# POWER_CON.net
KiCad netlist of a schematic drawn in Altium Designer
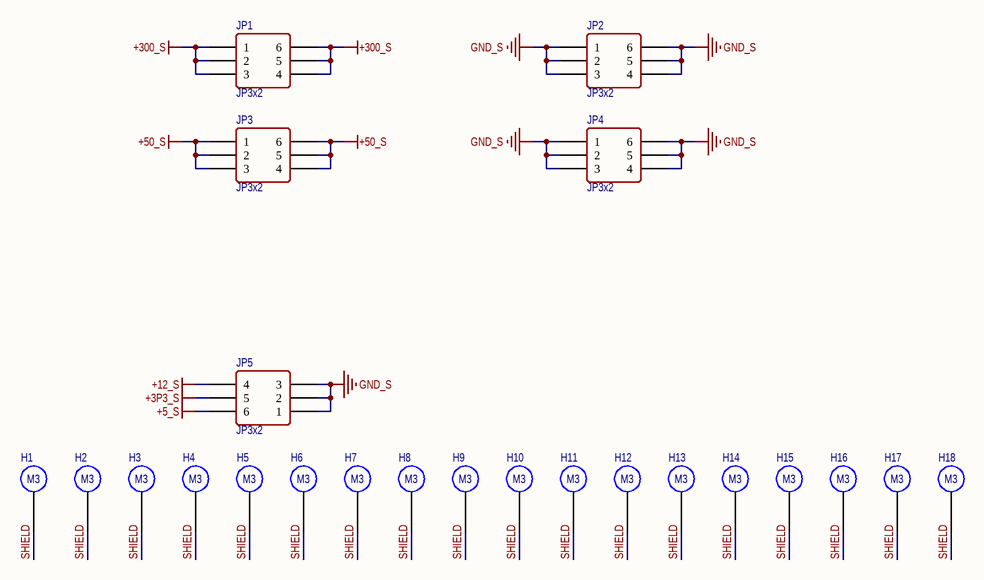
[diagram p0: POWER_CON.SchDoc]

(export (version "E")
  (design (tool "Eeschema 10.0.6"))
  (components
    (comp (ref "H1") (value "M3") (footprint "M3") (libsource (lib "Library") (part "M3")))
    (comp (ref "H2") (value "M3") (footprint "M3") (libsource (lib "Library") (part "M3")))
    (comp (ref "H3") (value "M3") (footprint "M3") (libsource (lib "Library") (part "M3")))
    (comp (ref "H4") (value "M3") (footprint "M3") (libsource (lib "Library") (part "M3")))
    (comp (ref "H5") (value "M3") (footprint "M3") (libsource (lib "Library") (part "M3")))
    (comp (ref "H6") (value "M3") (footprint "M3") (libsource (lib "Library") (part "M3")))
    (comp (ref "H7") (value "M3") (footprint "M3") (libsource (lib "Library") (part "M3")))
    (comp (ref "H8") (value "M3") (footprint "M3") (libsource (lib "Library") (part "M3")))
    (comp (ref "H9") (value "M3") (footprint "M3") (libsource (lib "Library") (part "M3")))
    (comp (ref "H10") (value "M3") (footprint "M3") (libsource (lib "Library") (part "M3")))
    (comp (ref "H11") (value "M3") (footprint "M3") (libsource (lib "Library") (part "M3")))
    (comp (ref "H12") (value "M3") (footprint "M3") (libsource (lib "Library") (part "M3")))
    (comp (ref "H13") (value "M3") (footprint "M3") (libsource (lib "Library") (part "M3")))
    (comp (ref "H14") (value "M3") (footprint "M3") (libsource (lib "Library") (part "M3")))
    (comp (ref "H15") (value "M3") (footprint "M3") (libsource (lib "Library") (part "M3")))
    (comp (ref "H16") (value "M3") (footprint "M3") (libsource (lib "Library") (part "M3")))
    (comp (ref "H17") (value "M3") (footprint "M3") (libsource (lib "Library") (part "M3")))
    (comp (ref "H18") (value "M3") (footprint "M3") (libsource (lib "Library") (part "M3")))
    (comp (ref "JP1")
      (value "JP3x2")
      (footprint "JP3-C2T")
      (description "CONN RCPT 6POS 0.1 GOLD PCB")
      (fields
        (field (name "MANUFACTURER") "Würth Elektronik eiSos GmbH")
        (field (name "PARTNO") "61300621821")
        (field (name "CREATED BY") "Karrer Zheng")
      )
      (libsource (lib "Library") (part "JP3x2"))
    )
    (comp (ref "JP2")
      (value "JP3x2")
      (footprint "JP3-C2T")
      (description "CONN RCPT 6POS 0.1 GOLD PCB")
      (fields
        (field (name "MANUFACTURER") "Würth Elektronik eiSos GmbH")
        (field (name "PARTNO") "61300621821")
        (field (name "CREATED BY") "Karrer Zheng")
      )
      (libsource (lib "Library") (part "JP3x2"))
    )
    (comp (ref "JP3")
      (value "JP3x2")
      (footprint "JP3-C2T")
      (description "CONN RCPT 6POS 0.1 GOLD PCB")
      (fields
        (field (name "MANUFACTURER") "Würth Elektronik eiSos GmbH")
        (field (name "PARTNO") "61300621821")
        (field (name "CREATED BY") "Karrer Zheng")
      )
      (libsource (lib "Library") (part "JP3x2"))
    )
    (comp (ref "JP4")
      (value "JP3x2")
      (footprint "JP3-C2T")
      (description "CONN RCPT 6POS 0.1 GOLD PCB")
      (fields
        (field (name "MANUFACTURER") "Würth Elektronik eiSos GmbH")
        (field (name "PARTNO") "61300621821")
        (field (name "CREATED BY") "Karrer Zheng")
      )
      (libsource (lib "Library") (part "JP3x2"))
    )
    (comp (ref "JP5")
      (value "JP3x2")
      (footprint "JP3-C2T")
      (description "CONN RCPT 6POS 0.1 GOLD PCB")
      (fields
        (field (name "MANUFACTURER") "Würth Elektronik eiSos GmbH")
        (field (name "PARTNO") "61300621821")
        (field (name "CREATED BY") "Karrer Zheng")
      )
      (libsource (lib "Library") (part "JP3x2"))
    )
  )
  (nets
    (net (code "1") (name "+3P3_S") (class "Default")
      (node (ref "JP5") (pin "5") (pinfunction "5_5") (pintype "passive"))
    )
    (net (code "2") (name "+5_S") (class "Default")
      (node (ref "JP5") (pin "6") (pinfunction "6_6") (pintype "passive"))
    )
    (net (code "3") (name "+12_S") (class "Default")
      (node (ref "JP5") (pin "4") (pinfunction "4_4") (pintype "passive"))
    )
    (net (code "4") (name "+50_S") (class "Default")
      (node (ref "JP3") (pin "1") (pinfunction "1_1") (pintype "passive"))
      (node (ref "JP3") (pin "2") (pinfunction "2_2") (pintype "passive"))
      (node (ref "JP3") (pin "3") (pinfunction "3_3") (pintype "passive"))
      (node (ref "JP3") (pin "4") (pinfunction "4_4") (pintype "passive"))
      (node (ref "JP3") (pin "5") (pinfunction "5_5") (pintype "passive"))
      (node (ref "JP3") (pin "6") (pinfunction "6_6") (pintype "passive"))
    )
    (net (code "5") (name "+300_S") (class "Default")
      (node (ref "JP1") (pin "1") (pinfunction "1_1") (pintype "passive"))
      (node (ref "JP1") (pin "2") (pinfunction "2_2") (pintype "passive"))
      (node (ref "JP1") (pin "3") (pinfunction "3_3") (pintype "passive"))
      (node (ref "JP1") (pin "4") (pinfunction "4_4") (pintype "passive"))
      (node (ref "JP1") (pin "5") (pinfunction "5_5") (pintype "passive"))
      (node (ref "JP1") (pin "6") (pinfunction "6_6") (pintype "passive"))
    )
    (net (code "6") (name "/SHIELD") (class "Default")
      (node (ref "H1") (pin "1") (pinfunction "76_1") (pintype "passive"))
      (node (ref "H10") (pin "1") (pinfunction "76_1") (pintype "passive"))
      (node (ref "H11") (pin "1") (pinfunction "76_1") (pintype "passive"))
      (node (ref "H12") (pin "1") (pinfunction "76_1") (pintype "passive"))
      (node (ref "H13") (pin "1") (pinfunction "76_1") (pintype "passive"))
      (node (ref "H14") (pin "1") (pinfunction "76_1") (pintype "passive"))
      (node (ref "H15") (pin "1") (pinfunction "76_1") (pintype "passive"))
      (node (ref "H16") (pin "1") (pinfunction "76_1") (pintype "passive"))
      (node (ref "H17") (pin "1") (pinfunction "76_1") (pintype "passive"))
      (node (ref "H18") (pin "1") (pinfunction "76_1") (pintype "passive"))
      (node (ref "H2") (pin "1") (pinfunction "76_1") (pintype "passive"))
      (node (ref "H3") (pin "1") (pinfunction "76_1") (pintype "passive"))
      (node (ref "H4") (pin "1") (pinfunction "76_1") (pintype "passive"))
      (node (ref "H5") (pin "1") (pinfunction "76_1") (pintype "passive"))
      (node (ref "H6") (pin "1") (pinfunction "76_1") (pintype "passive"))
      (node (ref "H7") (pin "1") (pinfunction "76_1") (pintype "passive"))
      (node (ref "H8") (pin "1") (pinfunction "76_1") (pintype "passive"))
      (node (ref "H9") (pin "1") (pinfunction "76_1") (pintype "passive"))
    )
    (net (code "7") (name "GND_S") (class "Default")
      (node (ref "JP2") (pin "1") (pinfunction "1_1") (pintype "passive"))
      (node (ref "JP2") (pin "2") (pinfunction "2_2") (pintype "passive"))
      (node (ref "JP2") (pin "3") (pinfunction "3_3") (pintype "passive"))
      (node (ref "JP2") (pin "4") (pinfunction "4_4") (pintype "passive"))
      (node (ref "JP2") (pin "5") (pinfunction "5_5") (pintype "passive"))
      (node (ref "JP2") (pin "6") (pinfunction "6_6") (pintype "passive"))
      (node (ref "JP4") (pin "1") (pinfunction "1_1") (pintype "passive"))
      (node (ref "JP4") (pin "2") (pinfunction "2_2") (pintype "passive"))
      (node (ref "JP4") (pin "3") (pinfunction "3_3") (pintype "passive"))
      (node (ref "JP4") (pin "4") (pinfunction "4_4") (pintype "passive"))
      (node (ref "JP4") (pin "5") (pinfunction "5_5") (pintype "passive"))
      (node (ref "JP4") (pin "6") (pinfunction "6_6") (pintype "passive"))
      (node (ref "JP5") (pin "1") (pinfunction "1_1") (pintype "passive"))
      (node (ref "JP5") (pin "2") (pinfunction "2_2") (pintype "passive"))
      (node (ref "JP5") (pin "3") (pinfunction "3_3") (pintype "passive"))
    )
  )
)
